# PaganiniClock.net
KiCad netlist of a schematic drawn in EAGLE
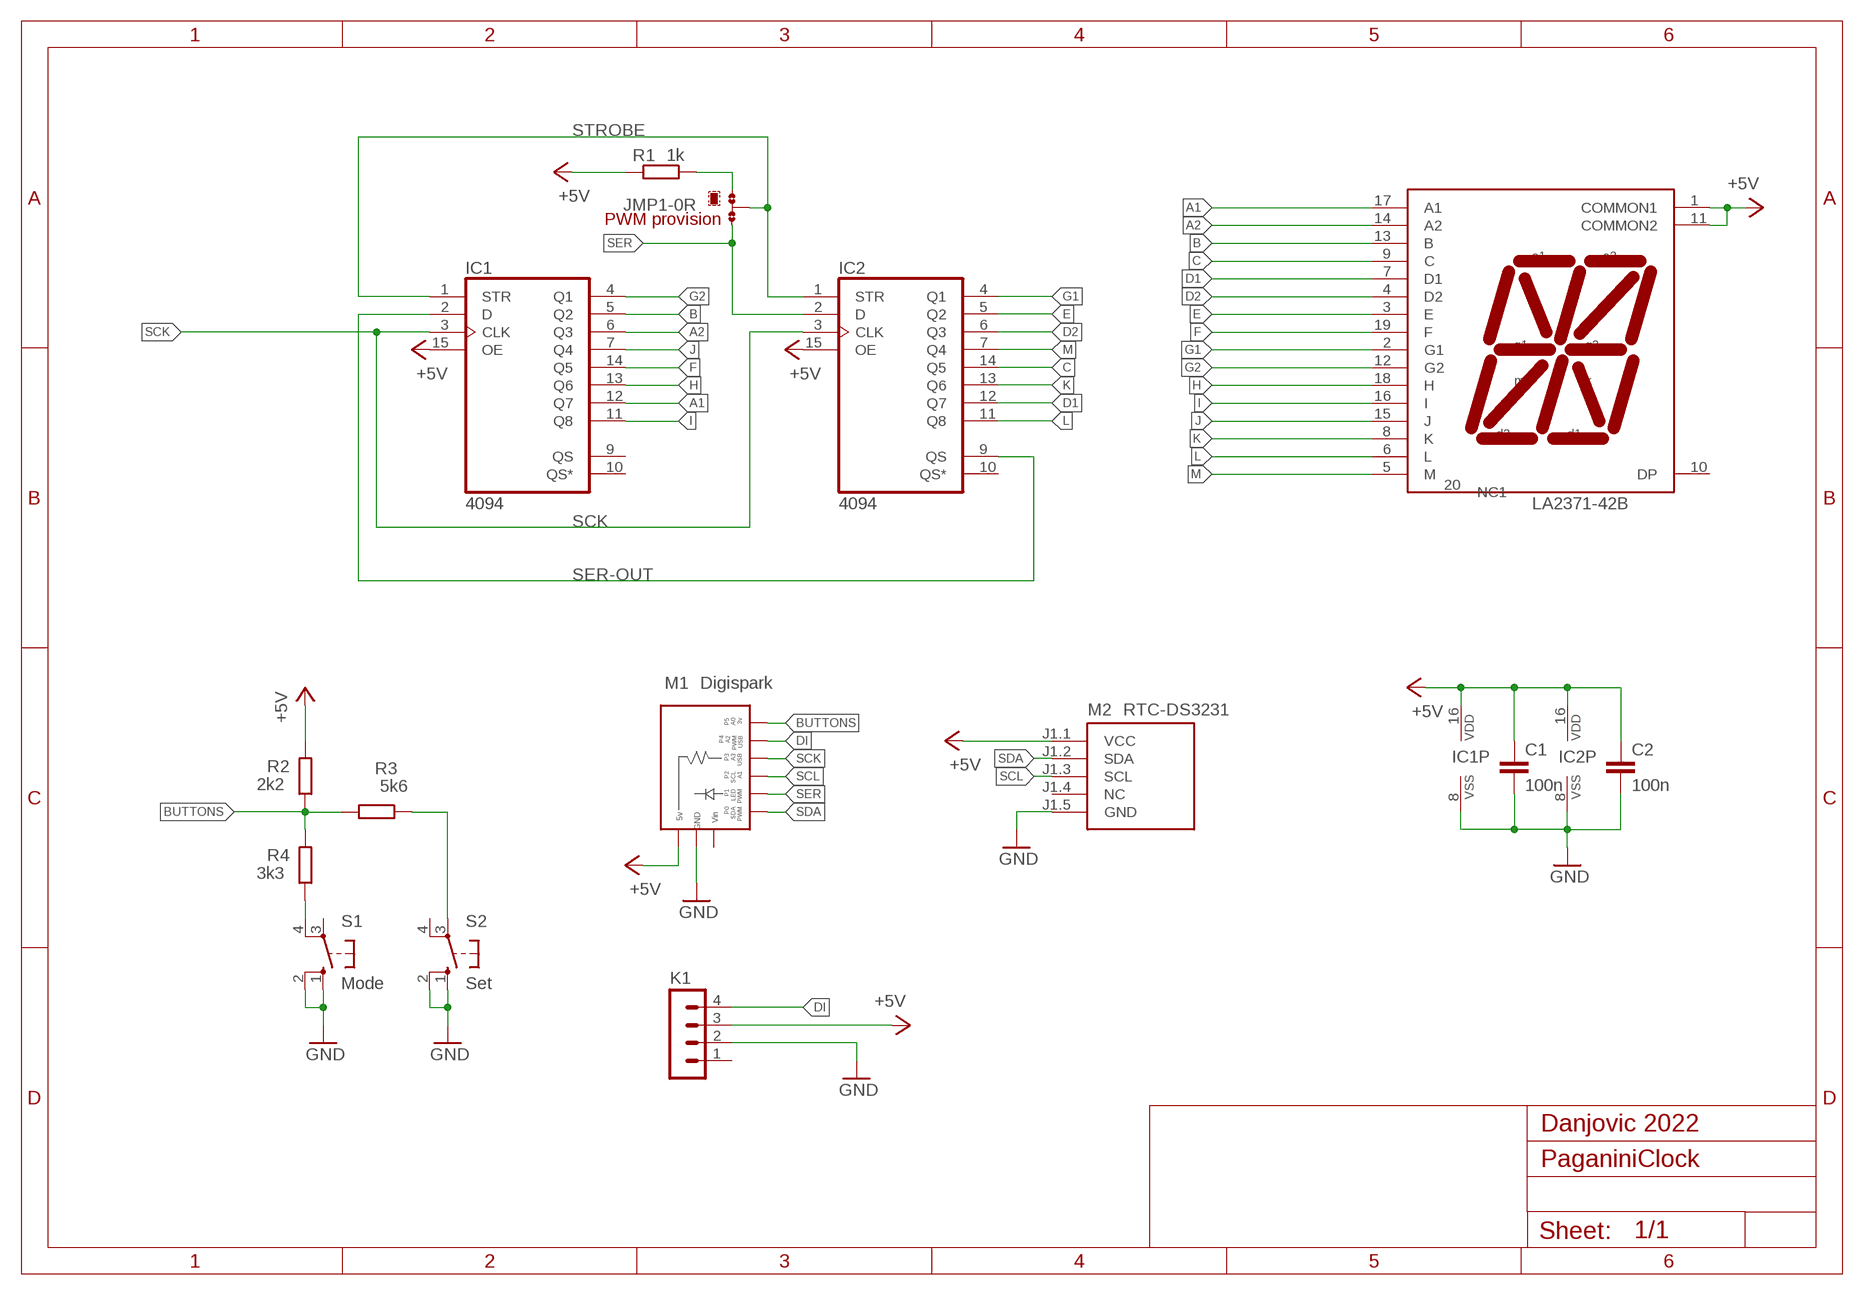
[diagram p0: schematic, sheet 1]

(export (version "E")
  (design (tool "Eeschema 10.0.6"))
  (components
    (comp (ref "C1")
      (value "100n")
      (footprint "eagle-import:C050-024X044L")
      (libsource (lib "eagle-import") (part "C-EUC050-024X044L"))
    )
    (comp (ref "C2")
      (value "100n")
      (footprint "eagle-import:C050-024X044L")
      (libsource (lib "eagle-import") (part "C-EUC050-024X044L"))
    )
    (comp (ref "DS1")
      (value "LA2371-42B")
      (footprint "eagle-import:LA(C)2371-42B-M1")
      (libsource (lib "eagle-import") (part "LA(C)2371-42B-M1{dblquote}{dblquote}"))
    )
    (comp (ref "IC1")
      (value "4094")
      (footprint "eagle-import:DIL16R")
      (libsource (lib "eagle-import") (part "4094"))
    )
    (comp (ref "IC2")
      (value "4094")
      (footprint "eagle-import:DIL16R")
      (libsource (lib "eagle-import") (part "4094"))
    )
    (comp (ref "JMP1")
      (value "DP_Option")
      (footprint "eagle-import:B0R-JMP")
      (libsource (lib "eagle-import") (part "0R-JUMPB"))
    )
    (comp (ref "K1")
      (value "MA04-1")
      (footprint "eagle-import:MA04-1")
      (libsource (lib "eagle-import") (part "MA04-1"))
    )
    (comp (ref "M1")
      (value "Digispark")
      (footprint "eagle-import:DIGISPARK_SOCKET")
      (libsource (lib "eagle-import") (part "DIGISPARK-SOCKET"))
    )
    (comp (ref "M2")
      (value "RTC-DS3231")
      (footprint "eagle-import:RTC-DS3231_SMALL")
      (libsource (lib "eagle-import") (part "RTC-DS3231"))
    )
    (comp (ref "R1")
      (value "1k")
      (footprint "eagle-import:0204_7L")
      (libsource (lib "eagle-import") (part "R-EU_0204/7L"))
    )
    (comp (ref "R2")
      (value "2k2")
      (footprint "eagle-import:0204_7L")
      (libsource (lib "eagle-import") (part "R-EU_0204/7L"))
    )
    (comp (ref "R3")
      (value "5k6")
      (footprint "eagle-import:0204_7L")
      (libsource (lib "eagle-import") (part "R-EU_0204/7L"))
    )
    (comp (ref "R4")
      (value "3k3")
      (footprint "eagle-import:0204_7L")
      (libsource (lib "eagle-import") (part "R-EU_0204/7L"))
    )
    (comp (ref "S1")
      (value "10-XX")
      (footprint "eagle-import:B3F-10XX")
      (fields (field (name "MPN") "B3F-1000"))
      (libsource (lib "eagle-import") (part "10-XX"))
    )
    (comp (ref "S2")
      (value "10-XX")
      (footprint "eagle-import:B3F-10XX")
      (fields (field (name "MPN") "B3F-1000"))
      (libsource (lib "eagle-import") (part "10-XX"))
    )
  )
  (nets
    (net (code "1") (name "+5V") (class "Default")
      (node (ref "C1") (pin "1") (pinfunction "1_1") (pintype "passive"))
      (node (ref "C2") (pin "1") (pinfunction "1_1") (pintype "passive"))
      (node (ref "DS1") (pin "1") (pinfunction "COMMON1_1") (pintype "bidirectional"))
      (node (ref "DS1") (pin "11") (pinfunction "COMMON2_11") (pintype "bidirectional"))
      (node (ref "IC1") (pin "15") (pinfunction "OE_15") (pintype "input"))
      (node (ref "IC1") (pin "16") (pinfunction "VDD_16") (pintype "power_in"))
      (node (ref "IC2") (pin "15") (pinfunction "OE_15") (pintype "input"))
      (node (ref "IC2") (pin "16") (pinfunction "VDD_16") (pintype "power_in"))
      (node (ref "K1") (pin "3") (pinfunction "3_3") (pintype "passive"))
      (node (ref "M1") (pin "5V") (pinfunction "5V_5V") (pintype "power_in"))
      (node (ref "M2") (pin "J1.1") (pinfunction "VCC_J1.1") (pintype "power_in"))
      (node (ref "R1") (pin "2") (pinfunction "2_2") (pintype "passive"))
      (node (ref "R2") (pin "2") (pinfunction "2_2") (pintype "passive"))
    )
    (net (code "2") (name "/SER-OUT") (class "Default")
      (node (ref "IC1") (pin "2") (pinfunction "D_2") (pintype "input"))
      (node (ref "IC2") (pin "9") (pinfunction "QS_9") (pintype "output"))
    )
    (net (code "3") (name "/STROBE") (class "Default")
      (node (ref "IC1") (pin "1") (pinfunction "STR_1") (pintype "input"))
      (node (ref "IC2") (pin "1") (pinfunction "STR_1") (pintype "input"))
      (node (ref "JMP1") (pin "2") (pinfunction "2_2") (pintype "passive"))
    )
    (net (code "4") (name "/VIN") (class "Default")
      (node (ref "M1") (pin "VIN") (pinfunction "VIN_VIN") (pintype "power_in"))
    )
    (net (code "5") (name "A1") (class "Default")
      (node (ref "DS1") (pin "17") (pinfunction "A1_17") (pintype "bidirectional"))
      (node (ref "IC1") (pin "12") (pinfunction "Q7_12") (pintype "output"))
    )
    (net (code "6") (name "A2") (class "Default")
      (node (ref "DS1") (pin "14") (pinfunction "A2_14") (pintype "bidirectional"))
      (node (ref "IC1") (pin "6") (pinfunction "Q3_6") (pintype "output"))
    )
    (net (code "7") (name "B") (class "Default")
      (node (ref "DS1") (pin "13") (pinfunction "B_13") (pintype "bidirectional"))
      (node (ref "IC1") (pin "5") (pinfunction "Q2_5") (pintype "output"))
    )
    (net (code "8") (name "BUTTONS") (class "Default")
      (node (ref "M1") (pin "P5") (pinfunction "P5_P5") (pintype "bidirectional"))
      (node (ref "R2") (pin "1") (pinfunction "1_1") (pintype "passive"))
      (node (ref "R3") (pin "2") (pinfunction "2_2") (pintype "passive"))
      (node (ref "R4") (pin "2") (pinfunction "2_2") (pintype "passive"))
    )
    (net (code "9") (name "C") (class "Default")
      (node (ref "DS1") (pin "9") (pinfunction "C_9") (pintype "bidirectional"))
      (node (ref "IC2") (pin "14") (pinfunction "Q5_14") (pintype "output"))
    )
    (net (code "10") (name "D1") (class "Default")
      (node (ref "DS1") (pin "7") (pinfunction "D1_7") (pintype "bidirectional"))
      (node (ref "IC2") (pin "12") (pinfunction "Q7_12") (pintype "output"))
    )
    (net (code "11") (name "D2") (class "Default")
      (node (ref "DS1") (pin "4") (pinfunction "D2_4") (pintype "bidirectional"))
      (node (ref "IC2") (pin "6") (pinfunction "Q3_6") (pintype "output"))
    )
    (net (code "12") (name "DI") (class "Default")
      (node (ref "K1") (pin "4") (pinfunction "4_4") (pintype "passive"))
      (node (ref "M1") (pin "P4") (pinfunction "P4_P4") (pintype "bidirectional"))
    )
    (net (code "13") (name "E") (class "Default")
      (node (ref "DS1") (pin "3") (pinfunction "E_3") (pintype "bidirectional"))
      (node (ref "IC2") (pin "5") (pinfunction "Q2_5") (pintype "output"))
    )
    (net (code "14") (name "F") (class "Default")
      (node (ref "DS1") (pin "19") (pinfunction "F_19") (pintype "bidirectional"))
      (node (ref "IC1") (pin "14") (pinfunction "Q5_14") (pintype "output"))
    )
    (net (code "15") (name "G1") (class "Default")
      (node (ref "DS1") (pin "2") (pinfunction "G1_2") (pintype "bidirectional"))
      (node (ref "IC2") (pin "4") (pinfunction "Q1_4") (pintype "output"))
    )
    (net (code "16") (name "G2") (class "Default")
      (node (ref "DS1") (pin "12") (pinfunction "G2_12") (pintype "bidirectional"))
      (node (ref "IC1") (pin "4") (pinfunction "Q1_4") (pintype "output"))
    )
    (net (code "17") (name "GND") (class "Default")
      (node (ref "C1") (pin "2") (pinfunction "2_2") (pintype "passive"))
      (node (ref "C2") (pin "2") (pinfunction "2_2") (pintype "passive"))
      (node (ref "IC1") (pin "8") (pinfunction "VSS_8") (pintype "power_in"))
      (node (ref "IC2") (pin "8") (pinfunction "VSS_8") (pintype "power_in"))
      (node (ref "K1") (pin "2") (pinfunction "2_2") (pintype "passive"))
      (node (ref "M1") (pin "GND") (pinfunction "GND_GND") (pintype "power_in"))
      (node (ref "M2") (pin "J1.5") (pinfunction "GND_J1.5") (pintype "power_in"))
      (node (ref "S1") (pin "1") (pinfunction "S_1") (pintype "passive"))
      (node (ref "S1") (pin "2") (pinfunction "S1_2") (pintype "passive"))
      (node (ref "S2") (pin "1") (pinfunction "S_1") (pintype "passive"))
      (node (ref "S2") (pin "2") (pinfunction "S1_2") (pintype "passive"))
    )
    (net (code "18") (name "H") (class "Default")
      (node (ref "DS1") (pin "18") (pinfunction "H_18") (pintype "bidirectional"))
      (node (ref "IC1") (pin "13") (pinfunction "Q6_13") (pintype "output"))
    )
    (net (code "19") (name "I") (class "Default")
      (node (ref "DS1") (pin "16") (pinfunction "I_16") (pintype "bidirectional"))
      (node (ref "IC1") (pin "11") (pinfunction "Q8_11") (pintype "output"))
    )
    (net (code "20") (name "J") (class "Default")
      (node (ref "DS1") (pin "15") (pinfunction "J_15") (pintype "bidirectional"))
      (node (ref "IC1") (pin "7") (pinfunction "Q4_7") (pintype "output"))
    )
    (net (code "21") (name "K") (class "Default")
      (node (ref "DS1") (pin "8") (pinfunction "K_8") (pintype "bidirectional"))
      (node (ref "IC2") (pin "13") (pinfunction "Q6_13") (pintype "output"))
    )
    (net (code "22") (name "L") (class "Default")
      (node (ref "DS1") (pin "6") (pinfunction "L_6") (pintype "bidirectional"))
      (node (ref "IC2") (pin "11") (pinfunction "Q8_11") (pintype "output"))
    )
    (net (code "23") (name "M") (class "Default")
      (node (ref "DS1") (pin "5") (pinfunction "M_5") (pintype "bidirectional"))
      (node (ref "IC2") (pin "7") (pinfunction "Q4_7") (pintype "output"))
    )
    (net (code "24") (name "Net-(JMP1-Pad1)") (class "Default")
      (node (ref "JMP1") (pin "1") (pinfunction "1_1") (pintype "passive"))
      (node (ref "R1") (pin "1") (pinfunction "1_1") (pintype "passive"))
    )
    (net (code "25") (name "Net-(S1-P1)") (class "Default")
      (node (ref "R4") (pin "1") (pinfunction "1_1") (pintype "passive"))
      (node (ref "S1") (pin "4") (pinfunction "P1_4") (pintype "passive"))
    )
    (net (code "26") (name "Net-(S2-P)") (class "Default")
      (node (ref "R3") (pin "1") (pinfunction "1_1") (pintype "passive"))
      (node (ref "S2") (pin "3") (pinfunction "P_3") (pintype "passive"))
    )
    (net (code "27") (name "SCK") (class "Default")
      (node (ref "IC1") (pin "3") (pinfunction "CLK_3") (pintype "input"))
      (node (ref "IC2") (pin "3") (pinfunction "CLK_3") (pintype "input"))
      (node (ref "M1") (pin "P3") (pinfunction "P3_P3") (pintype "bidirectional"))
    )
    (net (code "28") (name "SCL") (class "Default")
      (node (ref "M1") (pin "P2") (pinfunction "P2_P2") (pintype "bidirectional"))
      (node (ref "M2") (pin "J1.3") (pinfunction "SCL_J1.3") (pintype "bidirectional"))
    )
    (net (code "29") (name "SDA") (class "Default")
      (node (ref "M1") (pin "P0") (pinfunction "P0_P0") (pintype "bidirectional"))
      (node (ref "M2") (pin "J1.2") (pinfunction "SDA_J1.2") (pintype "bidirectional"))
    )
    (net (code "30") (name "SER") (class "Default")
      (node (ref "IC2") (pin "2") (pinfunction "D_2") (pintype "input"))
      (node (ref "JMP1") (pin "3") (pinfunction "3_3") (pintype "passive"))
      (node (ref "M1") (pin "P1") (pinfunction "P1_P1") (pintype "bidirectional"))
    )
    (net (code "31") (name "unconnected-(DS1-DP-Pad10)") (class "Default")
      (node (ref "DS1") (pin "10") (pinfunction "DP_10") (pintype "bidirectional"))
    )
    (net (code "32") (name "unconnected-(DS1-NC1-Pad20)") (class "Default")
      (node (ref "DS1") (pin "20") (pinfunction "NC1_20") (pintype "no_connect"))
    )
    (net (code "33") (name "unconnected-(IC1A-QS*-Pad10)") (class "Default")
      (node (ref "IC1") (pin "10") (pinfunction "QS*_10") (pintype "output"))
    )
    (net (code "34") (name "unconnected-(IC1A-QS-Pad9)") (class "Default")
      (node (ref "IC1") (pin "9") (pinfunction "QS_9") (pintype "output"))
    )
    (net (code "35") (name "unconnected-(IC2A-QS*-Pad10)") (class "Default")
      (node (ref "IC2") (pin "10") (pinfunction "QS*_10") (pintype "output"))
    )
    (net (code "36") (name "unconnected-(K1-Pad1)") (class "Default")
      (node (ref "K1") (pin "1") (pinfunction "1_1") (pintype "passive"))
    )
    (net (code "37") (name "unconnected-(M2-NC-PadJ1.4)") (class "Default")
      (node (ref "M2") (pin "J1.4") (pinfunction "NC_J1.4") (pintype "bidirectional"))
    )
    (net (code "38") (name "unconnected-(S1-P-Pad3)") (class "Default")
      (node (ref "S1") (pin "3") (pinfunction "P_3") (pintype "passive"))
    )
    (net (code "39") (name "unconnected-(S2-P1-Pad4)") (class "Default")
      (node (ref "S2") (pin "4") (pinfunction "P1_4") (pintype "passive"))
    )
  )
)
